# Nusbio_smd.net
KiCad netlist of a schematic drawn in EAGLE
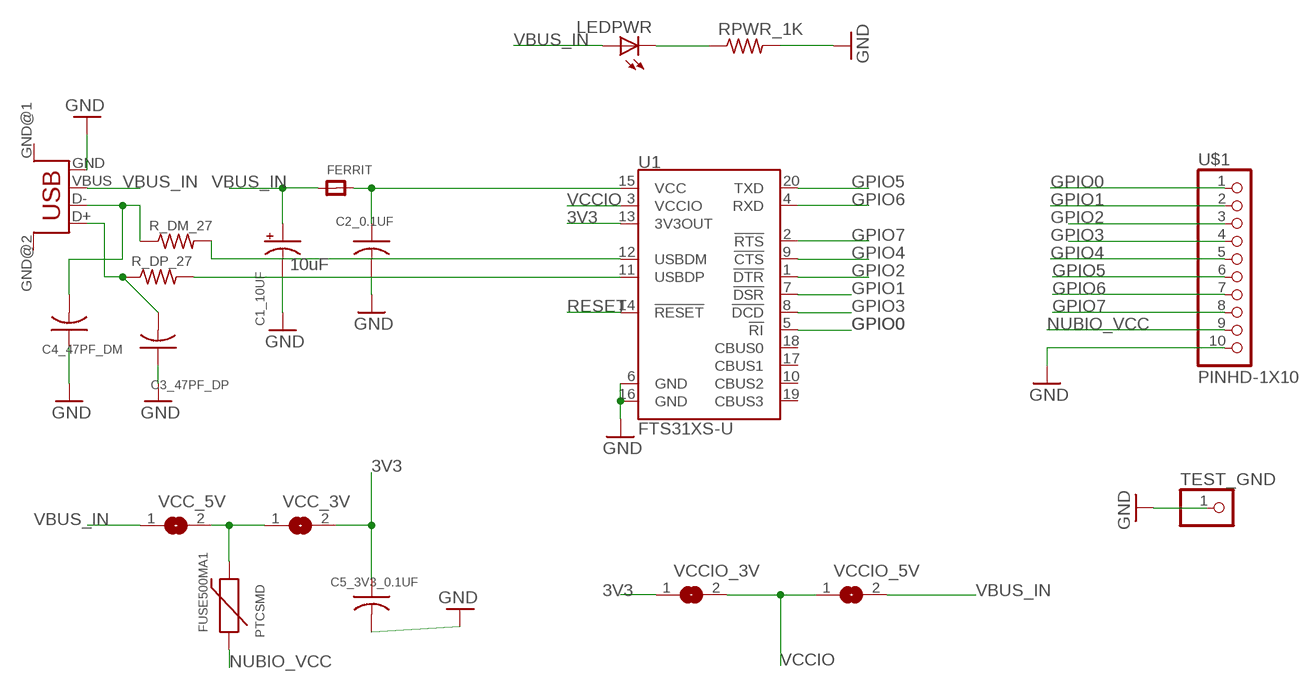
[diagram p0: schematic, sheet 1]

(export (version "E")
  (design (tool "Eeschema 10.0.6"))
  (components
    (comp (ref "C1_10UF")
      (value "10uF")
      (footprint "eagle-import:EIA3216")
      (libsource (lib "eagle-import") (part "10UF-16V-10%(TANT)"))
    )
    (comp (ref "C2_0.1UF")
      (value "C-USC1206")
      (footprint "eagle-import:C1206")
      (libsource (lib "eagle-import") (part "C-USC1206"))
    )
    (comp (ref "C3_47PF_DP")
      (value "C-USC1206")
      (footprint "eagle-import:C1206")
      (libsource (lib "eagle-import") (part "C-USC1206"))
    )
    (comp (ref "C4_47PF_DM")
      (value "C-USC1206")
      (footprint "eagle-import:C1206")
      (libsource (lib "eagle-import") (part "C-USC1206"))
    )
    (comp (ref "C5_3V3_0.1UF")
      (value "C-USC1206")
      (footprint "eagle-import:C1206")
      (libsource (lib "eagle-import") (part "C-USC1206"))
    )
    (comp (ref "FERRIT")
      (value "FERRITE_0805")
      (footprint "eagle-import:_0805")
      (libsource (lib "eagle-import") (part "FERRITE_0805"))
    )
    (comp (ref "FUSE500MA1")
      (value "PTCSMD")
      (footprint "eagle-import:PTC-1206")
      (libsource (lib "eagle-import") (part "PTCSMD"))
    )
    (comp (ref "LEDPWR")
      (value "LEDCHIPLED_0805")
      (footprint "eagle-import:CHIPLED_0805")
      (libsource (lib "eagle-import") (part "LEDCHIPLED_0805"))
    )
    (comp (ref "RPWR_1K")
      (value "R-US_R0805")
      (footprint "eagle-import:R0805")
      (libsource (lib "eagle-import") (part "R-US_R0805"))
    )
    (comp (ref "R_DM_27")
      (value "R-US_R0805")
      (footprint "eagle-import:R0805")
      (libsource (lib "eagle-import") (part "R-US_R0805"))
    )
    (comp (ref "R_DP_27")
      (value "R-US_R0805")
      (footprint "eagle-import:R0805")
      (libsource (lib "eagle-import") (part "R-US_R0805"))
    )
    (comp (ref "TEST_GND")
      (value "PINHD-1X1")
      (footprint "eagle-import:1X01")
      (libsource (lib "eagle-import") (part "PINHD-1X1"))
    )
    (comp (ref "U$1")
      (value "PINHD-1X10")
      (footprint "eagle-import:1X10-BIG")
      (libsource (lib "eagle-import") (part "PINHD-1X10"))
    )
    (comp (ref "U1")
      (value "FTS31XS-U")
      (footprint "eagle-import:SSOP20_L")
      (libsource (lib "eagle-import") (part "FT231XS"))
    )
    (comp (ref "USB_FEMALE")
      (value "USB")
      (footprint "eagle-import:USB-FEMALE-A-PTH")
      (libsource (lib "eagle-import") (part "USB"))
    )
    (comp (ref "VCCIO_3V")
      (value "SOLDERJUMPERREFLOW")
      (footprint "eagle-import:SOLDERJUMPER_REFLOW")
      (libsource (lib "eagle-import") (part "SOLDERJUMPERREFLOW"))
    )
    (comp (ref "VCCIO_5V")
      (value "SOLDERJUMPERREFLOW")
      (footprint "eagle-import:SOLDERJUMPER_REFLOW")
      (libsource (lib "eagle-import") (part "SOLDERJUMPERREFLOW"))
    )
    (comp (ref "VCC_3V")
      (value "SOLDERJUMPERREFLOW")
      (footprint "eagle-import:SOLDERJUMPER_REFLOW")
      (libsource (lib "eagle-import") (part "SOLDERJUMPERREFLOW"))
    )
    (comp (ref "VCC_5V")
      (value "SOLDERJUMPERREFLOW")
      (footprint "eagle-import:SOLDERJUMPER_REFLOW")
      (libsource (lib "eagle-import") (part "SOLDERJUMPERREFLOW"))
    )
  )
  (nets
    (net (code "1") (name "/3V3") (class "Default")
      (node (ref "C5_3V3_0.1UF") (pin "1") (pinfunction "1_1") (pintype "passive"))
      (node (ref "U1") (pin "13") (pinfunction "3V3OUT_13") (pintype "bidirectional"))
      (node (ref "VCCIO_3V") (pin "1") (pinfunction "1_1") (pintype "passive"))
      (node (ref "VCC_3V") (pin "2") (pinfunction "2_2") (pintype "passive"))
    )
    (net (code "2") (name "/GPIO0") (class "Default")
      (node (ref "U$1") (pin "1") (pinfunction "1_1") (pintype "passive"))
      (node (ref "U1") (pin "5") (pinfunction "~{RI}_5") (pintype "bidirectional"))
    )
    (net (code "3") (name "/GPIO1") (class "Default")
      (node (ref "U$1") (pin "2") (pinfunction "2_2") (pintype "passive"))
      (node (ref "U1") (pin "7") (pinfunction "~{DSR}_7") (pintype "bidirectional"))
    )
    (net (code "4") (name "/GPIO2") (class "Default")
      (node (ref "U$1") (pin "3") (pinfunction "3_3") (pintype "passive"))
      (node (ref "U1") (pin "1") (pinfunction "~{DTR}_1") (pintype "bidirectional"))
    )
    (net (code "5") (name "/GPIO3") (class "Default")
      (node (ref "U$1") (pin "4") (pinfunction "4_4") (pintype "passive"))
      (node (ref "U1") (pin "8") (pinfunction "~{DCD}_8") (pintype "bidirectional"))
    )
    (net (code "6") (name "/GPIO4") (class "Default")
      (node (ref "U$1") (pin "5") (pinfunction "5_5") (pintype "passive"))
      (node (ref "U1") (pin "9") (pinfunction "~{CTS}_9") (pintype "bidirectional"))
    )
    (net (code "7") (name "/GPIO5") (class "Default")
      (node (ref "U$1") (pin "6") (pinfunction "6_6") (pintype "passive"))
      (node (ref "U1") (pin "20") (pinfunction "TXD_20") (pintype "bidirectional"))
    )
    (net (code "8") (name "/GPIO6") (class "Default")
      (node (ref "U$1") (pin "7") (pinfunction "7_7") (pintype "passive"))
      (node (ref "U1") (pin "4") (pinfunction "RXD_4") (pintype "bidirectional"))
    )
    (net (code "9") (name "/GPIO7") (class "Default")
      (node (ref "U$1") (pin "8") (pinfunction "8_8") (pintype "passive"))
      (node (ref "U1") (pin "2") (pinfunction "~{RTS}_2") (pintype "bidirectional"))
    )
    (net (code "10") (name "/NUBIO_VCC") (class "Default")
      (node (ref "FUSE500MA1") (pin "1") (pinfunction "1_1") (pintype "bidirectional"))
      (node (ref "U$1") (pin "9") (pinfunction "9_9") (pintype "passive"))
    )
    (net (code "11") (name "/RESET") (class "Default")
      (node (ref "U1") (pin "14") (pinfunction "~{RESET}_14") (pintype "bidirectional"))
    )
    (net (code "12") (name "/VBUS_IN") (class "Default")
      (node (ref "C1_10UF") (pin "A") (pinfunction "+_A") (pintype "passive"))
      (node (ref "FERRIT") (pin "1") (pinfunction "P$1_1") (pintype "passive"))
      (node (ref "LEDPWR") (pin "A") (pinfunction "A_A") (pintype "passive"))
      (node (ref "USB_FEMALE") (pin "VBUS") (pinfunction "VBUS_VBUS") (pintype "bidirectional"))
      (node (ref "VCCIO_5V") (pin "2") (pinfunction "2_2") (pintype "passive"))
      (node (ref "VCC_5V") (pin "1") (pinfunction "1_1") (pintype "passive"))
    )
    (net (code "13") (name "/VCCIO") (class "Default")
      (node (ref "U1") (pin "3") (pinfunction "VCCIO_3") (pintype "bidirectional"))
      (node (ref "VCCIO_3V") (pin "2") (pinfunction "2_2") (pintype "passive"))
      (node (ref "VCCIO_5V") (pin "1") (pinfunction "1_1") (pintype "passive"))
    )
    (net (code "14") (name "GND") (class "Default")
      (node (ref "C1_10UF") (pin "C") (pinfunction "-_C") (pintype "passive"))
      (node (ref "C2_0.1UF") (pin "2") (pinfunction "2_2") (pintype "passive"))
      (node (ref "C3_47PF_DP") (pin "1") (pinfunction "1_1") (pintype "passive"))
      (node (ref "C4_47PF_DM") (pin "1") (pinfunction "1_1") (pintype "passive"))
      (node (ref "C5_3V3_0.1UF") (pin "2") (pinfunction "2_2") (pintype "passive"))
      (node (ref "RPWR_1K") (pin "2") (pinfunction "2_2") (pintype "passive"))
      (node (ref "TEST_GND") (pin "1") (pinfunction "1_1") (pintype "passive"))
      (node (ref "U$1") (pin "10") (pinfunction "10_10") (pintype "passive"))
      (node (ref "U1") (pin "16") (pinfunction "GND_16") (pintype "bidirectional"))
      (node (ref "U1") (pin "6") (pinfunction "GND_6") (pintype "bidirectional"))
      (node (ref "USB_FEMALE") (pin "GND") (pinfunction "GND_GND") (pintype "bidirectional"))
    )
    (net (code "15") (name "Net-(C3_47PF_DP-Pad2)") (class "Default")
      (node (ref "C3_47PF_DP") (pin "2") (pinfunction "2_2") (pintype "passive"))
      (node (ref "R_DP_27") (pin "1") (pinfunction "1_1") (pintype "passive"))
      (node (ref "USB_FEMALE") (pin "D+") (pinfunction "D+_D+") (pintype "bidirectional"))
    )
    (net (code "16") (name "Net-(C4_47PF_DM-Pad2)") (class "Default")
      (node (ref "C4_47PF_DM") (pin "2") (pinfunction "2_2") (pintype "passive"))
      (node (ref "R_DM_27") (pin "1") (pinfunction "1_1") (pintype "passive"))
      (node (ref "USB_FEMALE") (pin "D-") (pinfunction "D-_D-") (pintype "bidirectional"))
    )
    (net (code "17") (name "Net-(FERRIT-P$2)") (class "Default")
      (node (ref "C2_0.1UF") (pin "1") (pinfunction "1_1") (pintype "passive"))
      (node (ref "FERRIT") (pin "2") (pinfunction "P$2_2") (pintype "passive"))
      (node (ref "U1") (pin "15") (pinfunction "VCC_15") (pintype "bidirectional"))
    )
    (net (code "18") (name "Net-(FUSE500MA1-Pad2)") (class "Default")
      (node (ref "FUSE500MA1") (pin "2") (pinfunction "2_2") (pintype "bidirectional"))
      (node (ref "VCC_3V") (pin "1") (pinfunction "1_1") (pintype "passive"))
      (node (ref "VCC_5V") (pin "2") (pinfunction "2_2") (pintype "passive"))
    )
    (net (code "19") (name "Net-(LEDPWR-PadC)") (class "Default")
      (node (ref "LEDPWR") (pin "C") (pinfunction "C_C") (pintype "passive"))
      (node (ref "RPWR_1K") (pin "1") (pinfunction "1_1") (pintype "passive"))
    )
    (net (code "20") (name "Net-(U1-USBDM)") (class "Default")
      (node (ref "R_DM_27") (pin "2") (pinfunction "2_2") (pintype "passive"))
      (node (ref "U1") (pin "12") (pinfunction "USBDM_12") (pintype "bidirectional"))
    )
    (net (code "21") (name "Net-(U1-USBDP)") (class "Default")
      (node (ref "R_DP_27") (pin "2") (pinfunction "2_2") (pintype "passive"))
      (node (ref "U1") (pin "11") (pinfunction "USBDP_11") (pintype "bidirectional"))
    )
    (net (code "22") (name "unconnected-(U1-CBUS0-Pad18)") (class "Default")
      (node (ref "U1") (pin "18") (pinfunction "CBUS0_18") (pintype "bidirectional"))
    )
    (net (code "23") (name "unconnected-(U1-CBUS1-Pad17)") (class "Default")
      (node (ref "U1") (pin "17") (pinfunction "CBUS1_17") (pintype "bidirectional"))
    )
    (net (code "24") (name "unconnected-(U1-CBUS2-Pad10)") (class "Default")
      (node (ref "U1") (pin "10") (pinfunction "CBUS2_10") (pintype "bidirectional"))
    )
    (net (code "25") (name "unconnected-(U1-CBUS3-Pad19)") (class "Default")
      (node (ref "U1") (pin "19") (pinfunction "CBUS3_19") (pintype "bidirectional"))
    )
    (net (code "26") (name "unconnected-(USB_FEMALE-GND-PadGND@1)") (class "Default")
      (node (ref "USB_FEMALE") (pin "GND@1") (pinfunction "GND_GND@1") (pintype "bidirectional"))
    )
    (net (code "27") (name "unconnected-(USB_FEMALE-GND-PadGND@2)") (class "Default")
      (node (ref "USB_FEMALE") (pin "GND@2") (pinfunction "GND_GND@2") (pintype "bidirectional"))
    )
  )
)
